# CSI2-ORIN-NANO_Rev01.net
KiCad netlist of a schematic drawn in Altium Designer
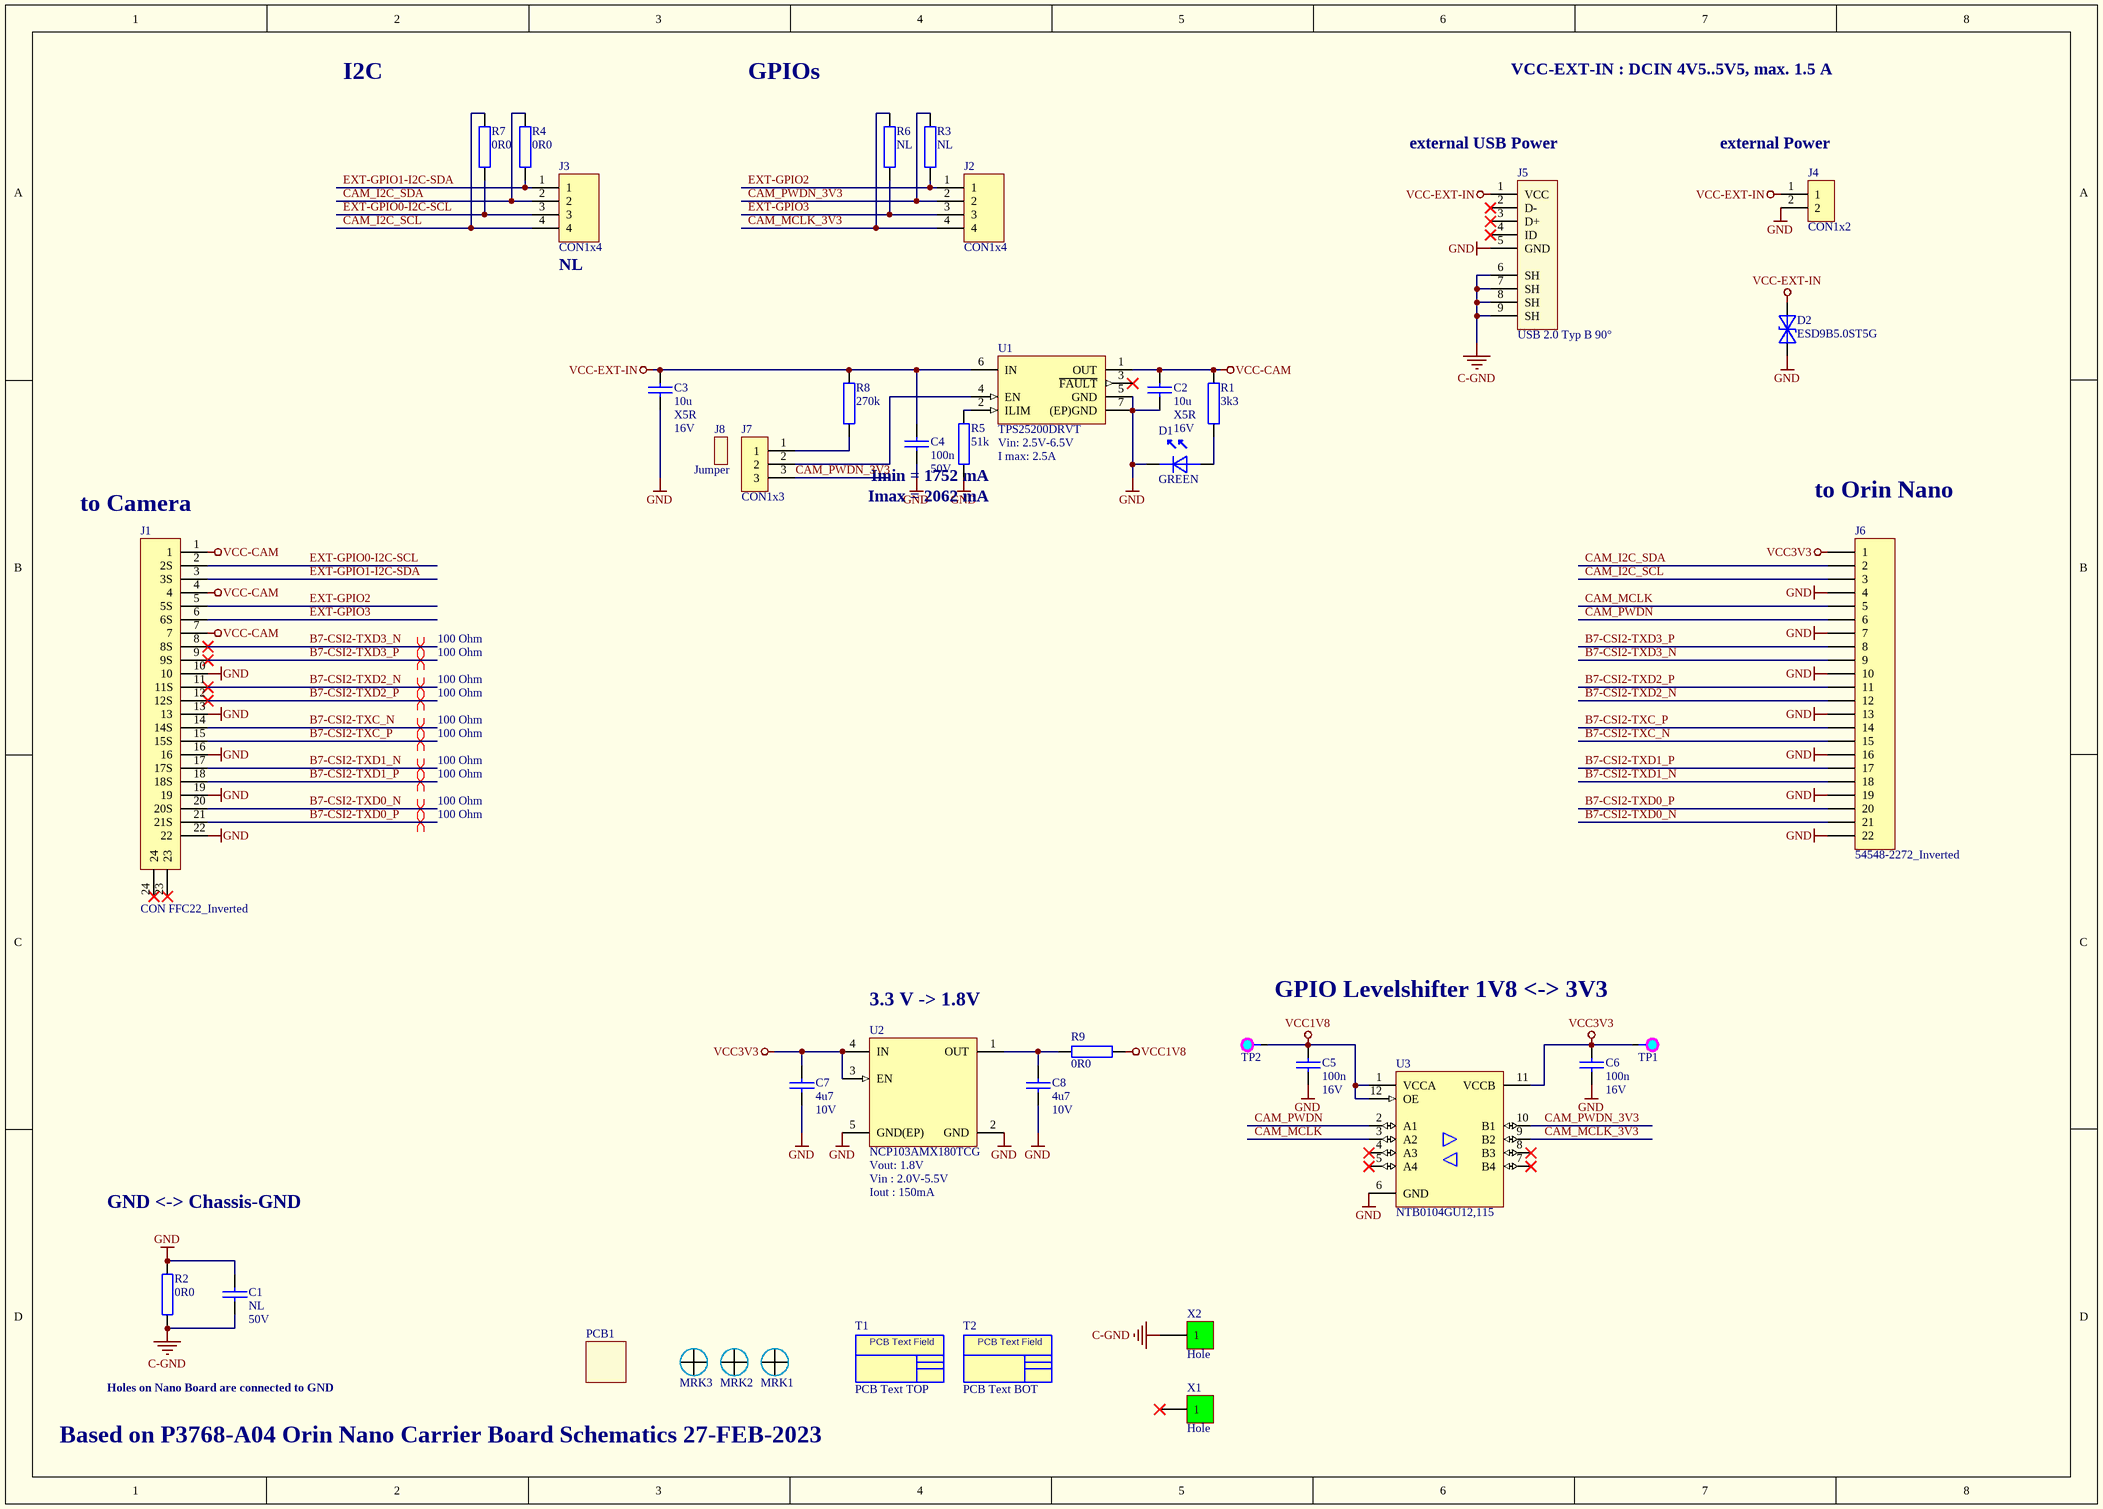
[diagram p0: CSI2-ORIN-NANO_Rev01.SchDoc]

(export (version "E")
  (design (tool "Eeschema 10.0.6"))
  (components
    (comp (ref "C1")
      (value "NL")
      (footprint "C-0603_1.0")
      (description "Capacitor Ceramic SMD/0603/50V/X7R/10%")
      (fields
        (field (name "MANUFACTURER") "several")
        (field (name "TOLERANCE") "10%")
        (field (name "VOLTAGE") "50V")
      )
      (libsource (lib "AVT_KHK_Lib") (part "C X 0603"))
    )
    (comp (ref "C2")
      (value "10u")
      (footprint "C-0805_1.4")
      (description "Capacitor Ceramic SMD/0805/16V/X5R/10%")
      (fields
        (field (name "KHK PART NUMBER") "K8340151")
        (field (name "MANUFACTURER") "several")
        (field (name "DIELECTRIC") "X5R")
        (field (name "VOLTAGE") "16V")
      )
      (libsource (lib "AVT_KHK_Lib") (part "C 10U 16V X5R 0805"))
    )
    (comp (ref "C3")
      (value "10u")
      (footprint "C-0805_1.4")
      (description "Capacitor Ceramic SMD/0805/16V/X5R/10%")
      (fields
        (field (name "KHK PART NUMBER") "K8340151")
        (field (name "MANUFACTURER") "several")
        (field (name "DIELECTRIC") "X5R")
        (field (name "VOLTAGE") "16V")
      )
      (libsource (lib "AVT_KHK_Lib") (part "C 10U 16V X5R 0805"))
    )
    (comp (ref "C4")
      (value "100n")
      (footprint "C-0603_1.0")
      (description "Capacitor Ceramic SMD/0603/50V/X7R/10%")
      (fields
        (field (name "KHK PART NUMBER") "K8340023")
        (field (name "MANUFACTURER") "several")
        (field (name "VOLTAGE") "50V")
      )
      (libsource (lib "AVT_KHK_Lib") (part "C 100N 50V X7R 0603"))
    )
    (comp (ref "C5")
      (value "100n")
      (footprint "C-0402_0.55")
      (description "Capacitor Ceramic SMD/0402/16V/X7R/10%")
      (fields
        (field (name "KHK PART NUMBER") "K8340114")
        (field (name "MANUFACTURER") "several")
        (field (name "VOLTAGE") "16V")
      )
      (libsource (lib "AVT_KHK_Lib") (part "C 100N 10% 16V X7R 402"))
    )
    (comp (ref "C6")
      (value "100n")
      (footprint "C-0402_0.55")
      (description "Capacitor Ceramic SMD/0402/16V/X7R/10%")
      (fields
        (field (name "KHK PART NUMBER") "K8340114")
        (field (name "MANUFACTURER") "several")
        (field (name "VOLTAGE") "16V")
      )
      (libsource (lib "AVT_KHK_Lib") (part "C 100N 10% 16V X7R 402"))
    )
    (comp (ref "C7")
      (value "4u7")
      (footprint "C-0603_1.0")
      (description "Capacitor Ceramic SMD/0603/10V/X5R/10%")
      (fields
        (field (name "KHK PART NUMBER") "1431")
        (field (name "MANUFACTURER") "several")
        (field (name "VOLTAGE") "10V")
      )
      (libsource (lib "AVT_KHK_Lib") (part "C 4U7 10V X5R 0603"))
    )
    (comp (ref "C8")
      (value "4u7")
      (footprint "C-0603_1.0")
      (description "Capacitor Ceramic SMD/0603/10V/X5R/10%")
      (fields
        (field (name "KHK PART NUMBER") "1431")
        (field (name "MANUFACTURER") "several")
        (field (name "VOLTAGE") "10V")
      )
      (libsource (lib "AVT_KHK_Lib") (part "C 4U7 10V X5R 0603"))
    )
    (comp (ref "D1")
      (value "GREEN")
      (footprint "D-0603-LED")
      (description "Chip LED green 430mcd")
      (fields (field (name "KHK PART NUMBER") "8172") (field (name "MANUFACTURER") "Würth"))
      (libsource (lib "AVT_KHK_Lib") (part "D LED 0603 green"))
    )
    (comp (ref "D2")
      (value "ESD9B5.0ST5G")
      (footprint "D-SOD923")
      (description "DIODE TVS; 400W; 5.8-7.8V; BIDIRECT")
      (fields (field (name "KHK PART NUMBER") "7250") (field (name "MANUFACTURER") "ON Semiconductor"))
      (libsource (lib "AVT_KHK_Lib") (part "D ESD9B5.0ST5G"))
    )
    (comp (ref "J1")
      (value "CON FFC22_Inverted")
      (footprint "J-FH55-22S-0.5SH - Inverted Pins")
      (description "FFC Connector 0.5mm shielded")
      (fields
        (field (name "KHK PART NUMBER") "10357")
        (field (name "MANUFACTURER PART NUMBER") "FH55-22S-0.5SH")
      )
      (libsource (lib "AVT_KHK_Lib") (part "CON FFC22_FH55-22S-0.5SH_Inverted"))
    )
    (comp (ref "J2")
      (value "CON1x4")
      (footprint "CON 1x4 RM2.54")
      (fields (field (name "MANUFACTURER") "several") (field (name "KHK PART NUMBER") "15343"))
      (libsource (lib "AVT_KHK_Lib") (part "CON 1x4 2.54 several"))
    )
    (comp (ref "J3")
      (value "CON1x4")
      (footprint "CON 1x4 RM2.54")
      (fields (field (name "MANUFACTURER") "several") (field (name "KHK PART NUMBER") "15343"))
      (libsource (lib "AVT_KHK_Lib") (part "CON 1x4 2.54 several"))
    )
    (comp (ref "J4")
      (value "CON1x2")
      (footprint "CON 1x2 RM2.54")
      (fields (field (name "MANUFACTURER") "several") (field (name "KHK PART NUMBER") "15337"))
      (libsource (lib "AVT_KHK_Lib") (part "CON 1x2 2.54 several"))
    )
    (comp (ref "J5")
      (value "USB 2.0 Typ B 90°")
      (footprint "J-629105150521")
      (description "Micro USB 2.0 Typ B 90°")
      (fields (field (name "KHK PART NUMBER") "14360") (field (name "MANUFACTURER") "WE"))
      (libsource (lib "Connector") (part "CON USB 2.0 Typ B 90°"))
    )
    (comp (ref "J6")
      (value "54548-2272_Inverted")
      (footprint "J-MOLEX-545482272 - INVERTED PINS")
      (description "CON/W2B/FFC;22-pin;0.5mm;SMT;FEMALE;HORIZONTAL")
      (fields (field (name "KHK PART NUMBER") "20137") (field (name "MANUFACTURER PART NUMBER") "54548-2272"))
      (libsource (lib "AVT_KHK_Lib") (part "CON FFC22_54548-2272_Inverted"))
    )
    (comp (ref "J7")
      (value "CON1x3")
      (footprint "CON 1x3 RM2.54")
      (fields (field (name "MANUFACTURER") "several") (field (name "KHK PART NUMBER") "15338"))
      (libsource (lib "AVT_KHK_Lib") (part "CON 1x3 2.54 several"))
    )
    (comp (ref "J8")
      (value "Jumper")
      (footprint "J-JUMPER-2.54")
      (description "CON/JUMPER/STC02SYAN; 2-pin; 2.54mm; 3A; FEMALE; VERTICAL; BLACK")
      (fields (field (name "KHK PART NUMBER") "13444") (field (name "MANUFACTURER") "several"))
      (libsource (lib "AVT_KHK_Lib") (part "CON Jumper 2.54mm"))
    )
    (comp (ref "MRK1")
      (value "Marker Single Layer")
      (footprint "PCB_Marker_Pad_top")
      (description "Position Marker for PCBs")
      (libsource (lib "AVT_KHK_Lib") (part "PCB Marker Pad Single Layer"))
    )
    (comp (ref "MRK2")
      (value "Marker Single Layer")
      (footprint "PCB_Marker_Pad_top")
      (description "Position Marker for PCBs")
      (libsource (lib "AVT_KHK_Lib") (part "PCB Marker Pad Single Layer"))
    )
    (comp (ref "MRK3")
      (value "Marker Single Layer")
      (footprint "PCB_Marker_Pad_top")
      (description "Position Marker for PCBs")
      (libsource (lib "AVT_KHK_Lib") (part "PCB Marker Pad Single Layer"))
    )
    (comp (ref "PCB1")
      (value "~")
      (description "PCB ML04")
      (fields (field (name "MANUFACTURER") "several"))
      (libsource (lib "AVT_KHK_Lib") (part "PCB"))
    )
    (comp (ref "R1")
      (value "3k3")
      (footprint "R-0603_0.6")
      (description "Standard Resistor SMD/0603/1%/100mW/TK100")
      (fields (field (name "KHK PART NUMBER") "K8250070") (field (name "MANUFACTURER") "several"))
      (libsource (lib "AVT_KHK_Lib") (part "R 3K3 1% 0603"))
    )
    (comp (ref "R2")
      (value "0R0")
      (footprint "R-0603_0.6")
      (description "Standard Resistor SMD/0603/1%/100mW/TK200")
      (fields (field (name "KHK PART NUMBER") "K8250041") (field (name "MANUFACTURER") "several"))
      (libsource (lib "AVT_KHK_Lib") (part "R 0R0 1% 0603"))
    )
    (comp (ref "R3")
      (value "NL")
      (footprint "R-0603_0.6")
      (description "Standard Resistor SMD/0603/1%/100mW/TK200")
      (fields (field (name "TOLERANCE") "1%"))
      (libsource (lib "AVT_KHK_Lib") (part "R X 0603"))
    )
    (comp (ref "R4")
      (value "0R0")
      (footprint "R-0603_0.6")
      (description "Standard Resistor SMD/0603/1%/100mW/TK100")
      (fields (field (name "KHK PART NUMBER") "K8250041") (field (name "MANUFACTURER") "several"))
      (libsource (lib "AVT_KHK_Lib") (part "R 0R0 1% 0603"))
    )
    (comp (ref "R5")
      (value "51k")
      (footprint "R-0603_0.6")
      (description "Standard Resistor SMD/0603/1%/100mW/TK100")
      (fields (field (name "KHK PART NUMBER") "K8250156") (field (name "MANUFACTURER") "several"))
      (libsource (lib "AVT_KHK_Lib") (part "R 51K 1% 0603"))
    )
    (comp (ref "R6")
      (value "NL")
      (footprint "R-0603_0.6")
      (description "Standard Resistor SMD/0603/1%/100mW/TK200")
      (fields (field (name "TOLERANCE") "1%"))
      (libsource (lib "AVT_KHK_Lib") (part "R X 0603"))
    )
    (comp (ref "R7")
      (value "0R0")
      (footprint "R-0603_0.6")
      (description "Standard Resistor SMD/0603/1%/100mW/TK100")
      (fields (field (name "KHK PART NUMBER") "K8250041") (field (name "MANUFACTURER") "several"))
      (libsource (lib "AVT_KHK_Lib") (part "R 0R0 1% 0603"))
    )
    (comp (ref "R8")
      (value "270k")
      (footprint "R-0603_0.6")
      (description "Standard Resistor SMD/0603/1%/100mW/TK100")
      (fields (field (name "KHK PART NUMBER") "K8250170") (field (name "MANUFACTURER") "several"))
      (libsource (lib "AVT_KHK_Lib") (part "R 270K 1% 0603"))
    )
    (comp (ref "R9")
      (value "0R0")
      (footprint "R-0603_0.6")
      (description "Standard Resistor SMD/0603/1%/100mW/TK100")
      (fields (field (name "KHK PART NUMBER") "K8250041") (field (name "MANUFACTURER") "several"))
      (libsource (lib "Passive") (part "R 0R0 1% 0603"))
    )
    (comp (ref "T1")
      (value "PCB Text TOP")
      (footprint "PCB TEXTFIELD TOP 2")
      (description "PCB Textfield TOP")
      (libsource (lib "AVT_KHK_Lib") (part "PCB TEXT FIELD TOP"))
    )
    (comp (ref "T2")
      (value "PCB Text BOT")
      (footprint "PCB TEXTFIELD BOT 2")
      (description "PCB Textfield BOT")
      (libsource (lib "AVT_KHK_Lib") (part "PCB TEXT FIELD BOT"))
    )
    (comp (ref "TP1")
      (value "TP")
      (footprint "TP_16_10")
      (description "Testpoint: Pad=1,6mm; Hole=1,0mm")
      (libsource (lib "AVT_KHK_Lib") (part "TP_16_10"))
    )
    (comp (ref "TP2")
      (value "TP")
      (footprint "TP_16_10")
      (description "Testpoint: Pad=1,6mm; Hole=1,0mm")
      (libsource (lib "AVT_KHK_Lib") (part "TP_16_10"))
    )
    (comp (ref "U1")
      (value "TPS25200DRVT")
      (footprint "IC-DFN06_2.0x2.0x0.8")
      (description "IC/PWR/LOADSW;2V5-6V5;2A5;0R099/6-WDFN/2x2x0.8mm")
      (fields
        (field (name "KHK PART NUMBER") "14277")
        (field (name "MANUFACTURER") "Texas Instruments")
        (field (name "VIN") "2.5V-6.5V")
        (field (name "I MAX") "2.5A")
      )
      (libsource (lib "AVT_KHK_Lib") (part "IC  TPS25200DRVT"))
    )
    (comp (ref "U2")
      (value "NCP103AMX180TCG")
      (footprint "IC-XDFN4_1.0x1.0x0.6")
      (description "IC/PWR/LDO;2V0-5V5;1V8;0A150/uDFN4/1x1x0.6mm")
      (fields
        (field (name "KHK PART NUMBER") "14922")
        (field (name "MANUFACTURER") "ON Semi")
        (field (name "VOUT") "1.8V")
        (field (name "VIN") "Vin : 2.0V-5.5V")
        (field (name "IOUT") "Iout : 150mA")
      )
      (libsource (lib "AVT_KHK_Lib") (part "IC NCP103AMX180TCG"))
    )
    (comp (ref "U3")
      (value "NTB0104GU12,115")
      (footprint "IC-XQFN12_1.7x2x0.5")
      (description "IC/LOGIC/Levelshifter;Auto-Dir;Bidirectional;Push-Pull;-40-+125°C/")
      (fields (field (name "MANUFACTURER") "NXP") (field (name "KHK PART NUMBER") "14383"))
      (libsource (lib "AVT_KHK_Lib") (part "IC NTB0104GU12,115"))
    )
    (comp (ref "X1")
      (value "Hole")
      (footprint "HOLE-2.6-5.0-DK")
      (description "HOLE M2.5")
      (libsource (lib "AVT_KHK_Lib") (part "PCB HOLE M2.5-5-DK"))
    )
    (comp (ref "X2")
      (value "Hole")
      (footprint "HOLE-2.6-5.0-DK")
      (description "HOLE M2.5")
      (libsource (lib "AVT_KHK_Lib") (part "PCB HOLE M2.5-5-DK"))
    )
  )
  (nets
    (net (code "1") (name "/B7-CSI2-TXC_N") (class "Default")
      (node (ref "J1") (pin "14") (pinfunction "14S_14") (pintype "passive"))
      (node (ref "J6") (pin "15") (pinfunction "15_15") (pintype "passive"))
    )
    (net (code "2") (name "/B7-CSI2-TXC_P") (class "Default")
      (node (ref "J1") (pin "15") (pinfunction "15S_15") (pintype "passive"))
      (node (ref "J6") (pin "14") (pinfunction "14_14") (pintype "passive"))
    )
    (net (code "3") (name "/B7-CSI2-TXD0_N") (class "Default")
      (node (ref "J1") (pin "20") (pinfunction "20S_20") (pintype "passive"))
      (node (ref "J6") (pin "21") (pinfunction "21_21") (pintype "passive"))
    )
    (net (code "4") (name "/B7-CSI2-TXD0_P") (class "Default")
      (node (ref "J1") (pin "21") (pinfunction "21S_21") (pintype "passive"))
      (node (ref "J6") (pin "20") (pinfunction "20_20") (pintype "passive"))
    )
    (net (code "5") (name "/B7-CSI2-TXD1_N") (class "Default")
      (node (ref "J1") (pin "17") (pinfunction "17S_17") (pintype "passive"))
      (node (ref "J6") (pin "18") (pinfunction "18_18") (pintype "passive"))
    )
    (net (code "6") (name "/B7-CSI2-TXD1_P") (class "Default")
      (node (ref "J1") (pin "18") (pinfunction "18S_18") (pintype "passive"))
      (node (ref "J6") (pin "17") (pinfunction "17_17") (pintype "passive"))
    )
    (net (code "7") (name "/B7-CSI2-TXD2_N") (class "Default")
      (node (ref "J1") (pin "11") (pinfunction "11S_11") (pintype "passive"))
      (node (ref "J6") (pin "12") (pinfunction "12_12") (pintype "passive"))
    )
    (net (code "8") (name "/B7-CSI2-TXD2_P") (class "Default")
      (node (ref "J1") (pin "12") (pinfunction "12S_12") (pintype "passive"))
      (node (ref "J6") (pin "11") (pinfunction "11_11") (pintype "passive"))
    )
    (net (code "9") (name "/B7-CSI2-TXD3_N") (class "Default")
      (node (ref "J1") (pin "8") (pinfunction "8S_8") (pintype "passive"))
      (node (ref "J6") (pin "9") (pinfunction "9_9") (pintype "passive"))
    )
    (net (code "10") (name "/B7-CSI2-TXD3_P") (class "Default")
      (node (ref "J1") (pin "9") (pinfunction "9S_9") (pintype "passive"))
      (node (ref "J6") (pin "8") (pinfunction "8_8") (pintype "passive"))
    )
    (net (code "11") (name "/CAM_I2C_SCL") (class "Default")
      (node (ref "J3") (pin "4") (pinfunction "4_4") (pintype "passive"))
      (node (ref "J6") (pin "3") (pinfunction "3_3") (pintype "passive"))
      (node (ref "R7") (pin "2") (pinfunction "2_2") (pintype "passive"))
    )
    (net (code "12") (name "/CAM_I2C_SDA") (class "Default")
      (node (ref "J3") (pin "2") (pinfunction "2_2") (pintype "passive"))
      (node (ref "J6") (pin "2") (pinfunction "2_2") (pintype "passive"))
      (node (ref "R4") (pin "2") (pinfunction "2_2") (pintype "passive"))
    )
    (net (code "13") (name "/CAM_MCLK") (class "Default")
      (node (ref "J6") (pin "5") (pinfunction "5_5") (pintype "passive"))
      (node (ref "U3") (pin "3") (pinfunction "A2_3") (pintype "bidirectional"))
    )
    (net (code "14") (name "/CAM_MCLK_3V3") (class "Default")
      (node (ref "J2") (pin "4") (pinfunction "4_4") (pintype "passive"))
      (node (ref "R6") (pin "2") (pinfunction "2_2") (pintype "passive"))
      (node (ref "U3") (pin "9") (pinfunction "B2_9") (pintype "bidirectional"))
    )
    (net (code "15") (name "/CAM_PWDN") (class "Default")
      (node (ref "J6") (pin "6") (pinfunction "6_6") (pintype "passive"))
      (node (ref "U3") (pin "2") (pinfunction "A1_2") (pintype "bidirectional"))
    )
    (net (code "16") (name "/CAM_PWDN_3V3") (class "Default")
      (node (ref "J2") (pin "2") (pinfunction "2_2") (pintype "passive"))
      (node (ref "J7") (pin "3") (pinfunction "3_3") (pintype "passive"))
      (node (ref "R3") (pin "2") (pinfunction "2_2") (pintype "passive"))
      (node (ref "U3") (pin "10") (pinfunction "B1_10") (pintype "bidirectional"))
    )
    (net (code "17") (name "/EXT-GPIO0-I2C-SCL") (class "Default")
      (node (ref "J1") (pin "2") (pinfunction "2S_2") (pintype "passive"))
      (node (ref "J3") (pin "3") (pinfunction "3_3") (pintype "passive"))
      (node (ref "R7") (pin "1") (pinfunction "1_1") (pintype "passive"))
    )
    (net (code "18") (name "/EXT-GPIO1-I2C-SDA") (class "Default")
      (node (ref "J1") (pin "3") (pinfunction "3S_3") (pintype "passive"))
      (node (ref "J3") (pin "1") (pinfunction "1_1") (pintype "passive"))
      (node (ref "R4") (pin "1") (pinfunction "1_1") (pintype "passive"))
    )
    (net (code "19") (name "/EXT-GPIO2") (class "Default")
      (node (ref "J1") (pin "5") (pinfunction "5S_5") (pintype "passive"))
      (node (ref "J2") (pin "1") (pinfunction "1_1") (pintype "passive"))
      (node (ref "R3") (pin "1") (pinfunction "1_1") (pintype "passive"))
    )
    (net (code "20") (name "/EXT-GPIO3") (class "Default")
      (node (ref "J1") (pin "6") (pinfunction "6S_6") (pintype "passive"))
      (node (ref "J2") (pin "3") (pinfunction "3_3") (pintype "passive"))
      (node (ref "R6") (pin "1") (pinfunction "1_1") (pintype "passive"))
    )
    (net (code "21") (name "C-GND") (class "Default")
      (node (ref "C1") (pin "2") (pinfunction "2_2") (pintype "passive"))
      (node (ref "J5") (pin "6") (pinfunction "SH_6") (pintype "passive"))
      (node (ref "J5") (pin "7") (pinfunction "SH_7") (pintype "passive"))
      (node (ref "J5") (pin "8") (pinfunction "SH_8") (pintype "passive"))
      (node (ref "J5") (pin "9") (pinfunction "SH_9") (pintype "passive"))
      (node (ref "R2") (pin "1") (pinfunction "1_1") (pintype "passive"))
      (node (ref "X2") (pin "1") (pinfunction "1_1") (pintype "passive"))
    )
    (net (code "22") (name "GND") (class "Default")
      (node (ref "C1") (pin "1") (pinfunction "1_1") (pintype "passive"))
      (node (ref "C2") (pin "2") (pinfunction "2_2") (pintype "passive"))
      (node (ref "C3") (pin "2") (pinfunction "2_2") (pintype "passive"))
      (node (ref "C4") (pin "2") (pinfunction "2_2") (pintype "passive"))
      (node (ref "C5") (pin "2") (pinfunction "2_2") (pintype "passive"))
      (node (ref "C6") (pin "2") (pinfunction "2_2") (pintype "passive"))
      (node (ref "C7") (pin "2") (pinfunction "2_2") (pintype "passive"))
      (node (ref "C8") (pin "2") (pinfunction "2_2") (pintype "passive"))
      (node (ref "D1") (pin "K") (pinfunction "2_K") (pintype "passive"))
      (node (ref "D2") (pin "A") (pinfunction "A_A") (pintype "passive"))
      (node (ref "J1") (pin "10") (pinfunction "10_10") (pintype "passive"))
      (node (ref "J1") (pin "13") (pinfunction "13_13") (pintype "passive"))
      (node (ref "J1") (pin "16") (pinfunction "16_16") (pintype "passive"))
      (node (ref "J1") (pin "19") (pinfunction "19_19") (pintype "passive"))
      (node (ref "J1") (pin "22") (pinfunction "22_22") (pintype "passive"))
      (node (ref "J4") (pin "2") (pinfunction "2_2") (pintype "passive"))
      (node (ref "J5") (pin "5") (pinfunction "GND_5") (pintype "passive"))
      (node (ref "J6") (pin "10") (pinfunction "10_10") (pintype "passive"))
      (node (ref "J6") (pin "13") (pinfunction "13_13") (pintype "passive"))
      (node (ref "J6") (pin "16") (pinfunction "16_16") (pintype "passive"))
      (node (ref "J6") (pin "19") (pinfunction "19_19") (pintype "passive"))
      (node (ref "J6") (pin "22") (pinfunction "22_22") (pintype "passive"))
      (node (ref "J6") (pin "4") (pinfunction "4_4") (pintype "passive"))
      (node (ref "J6") (pin "7") (pinfunction "7_7") (pintype "passive"))
      (node (ref "R2") (pin "2") (pinfunction "2_2") (pintype "passive"))
      (node (ref "R5") (pin "1") (pinfunction "1_1") (pintype "passive"))
      (node (ref "U1") (pin "5") (pinfunction "GND_5") (pintype "power_in"))
      (node (ref "U1") (pin "7") (pinfunction "(EP)GND_7") (pintype "power_in"))
      (node (ref "U2") (pin "2") (pinfunction "GND_2") (pintype "power_in"))
      (node (ref "U2") (pin "5") (pinfunction "GND(EP)_5") (pintype "power_in"))
      (node (ref "U3") (pin "6") (pinfunction "GND_6") (pintype "power_in"))
    )
    (net (code "23") (name "Net-(D1-1)") (class "Default")
      (node (ref "D1") (pin "A") (pinfunction "1_A") (pintype "passive"))
      (node (ref "R1") (pin "2") (pinfunction "2_2") (pintype "passive"))
    )
    (net (code "24") (name "Net-(J7-Pad1)") (class "Default")
      (node (ref "J7") (pin "1") (pinfunction "1_1") (pintype "passive"))
      (node (ref "R8") (pin "2") (pinfunction "2_2") (pintype "passive"))
    )
    (net (code "25") (name "Net-(U1-EN)") (class "Default")
      (node (ref "J7") (pin "2") (pinfunction "2_2") (pintype "passive"))
      (node (ref "U1") (pin "4") (pinfunction "EN_4") (pintype "input"))
    )
    (net (code "26") (name "Net-(U1-ILIM)") (class "Default")
      (node (ref "R5") (pin "2") (pinfunction "2_2") (pintype "passive"))
      (node (ref "U1") (pin "2") (pinfunction "ILIM_2") (pintype "input"))
    )
    (net (code "27") (name "Net-(U2-OUT)") (class "Default")
      (node (ref "C8") (pin "1") (pinfunction "1_1") (pintype "passive"))
      (node (ref "R9") (pin "1") (pinfunction "1_1") (pintype "passive"))
      (node (ref "U2") (pin "1") (pinfunction "OUT_1") (pintype "power_in"))
    )
    (net (code "28") (name "VCC-CAM") (class "Default")
      (node (ref "C2") (pin "1") (pinfunction "1_1") (pintype "passive"))
      (node (ref "J1") (pin "1") (pinfunction "1_1") (pintype "passive"))
      (node (ref "J1") (pin "4") (pinfunction "4_4") (pintype "passive"))
      (node (ref "J1") (pin "7") (pinfunction "7_7") (pintype "passive"))
      (node (ref "R1") (pin "1") (pinfunction "1_1") (pintype "passive"))
      (node (ref "U1") (pin "1") (pinfunction "OUT_1") (pintype "power_in"))
    )
    (net (code "29") (name "VCC-EXT-IN") (class "Default")
      (node (ref "C3") (pin "1") (pinfunction "1_1") (pintype "passive"))
      (node (ref "C4") (pin "1") (pinfunction "1_1") (pintype "passive"))
      (node (ref "D2") (pin "K") (pinfunction "K_K") (pintype "passive"))
      (node (ref "J4") (pin "1") (pinfunction "1_1") (pintype "passive"))
      (node (ref "J5") (pin "1") (pinfunction "VCC_1") (pintype "passive"))
      (node (ref "R8") (pin "1") (pinfunction "1_1") (pintype "passive"))
      (node (ref "U1") (pin "6") (pinfunction "IN_6") (pintype "power_in"))
    )
    (net (code "30") (name "VCC1V8") (class "Default")
      (node (ref "C5") (pin "1") (pinfunction "1_1") (pintype "passive"))
      (node (ref "R9") (pin "2") (pinfunction "2_2") (pintype "passive"))
      (node (ref "TP2") (pin "1") (pinfunction "1_1") (pintype "passive"))
      (node (ref "U3") (pin "1") (pinfunction "VCCA_1") (pintype "power_in"))
      (node (ref "U3") (pin "12") (pinfunction "OE_12") (pintype "input"))
    )
    (net (code "31") (name "VCC3V3") (class "Default")
      (node (ref "C6") (pin "1") (pinfunction "1_1") (pintype "passive"))
      (node (ref "C7") (pin "1") (pinfunction "1_1") (pintype "passive"))
      (node (ref "J6") (pin "1") (pinfunction "1_1") (pintype "passive"))
      (node (ref "TP1") (pin "1") (pinfunction "1_1") (pintype "passive"))
      (node (ref "U2") (pin "3") (pinfunction "EN_3") (pintype "input"))
      (node (ref "U2") (pin "4") (pinfunction "IN_4") (pintype "power_in"))
      (node (ref "U3") (pin "11") (pinfunction "VCCB_11") (pintype "power_in"))
    )
    (net (code "32") (name "unconnected-(J1-Pad23)") (class "Default")
      (node (ref "J1") (pin "23") (pinfunction "23_23") (pintype "passive+no_connect"))
    )
    (net (code "33") (name "unconnected-(J1-Pad24)") (class "Default")
      (node (ref "J1") (pin "24") (pinfunction "24_24") (pintype "passive+no_connect"))
    )
    (net (code "34") (name "unconnected-(J5-D+-Pad3)") (class "Default")
      (node (ref "J5") (pin "3") (pinfunction "D+_3") (pintype "passive+no_connect"))
    )
    (net (code "35") (name "unconnected-(J5-D--Pad2)") (class "Default")
      (node (ref "J5") (pin "2") (pinfunction "D-_2") (pintype "passive+no_connect"))
    )
    (net (code "36") (name "unconnected-(J5-ID-Pad4)") (class "Default")
      (node (ref "J5") (pin "4") (pinfunction "ID_4") (pintype "passive+no_connect"))
    )
    (net (code "37") (name "unconnected-(U1-~{FAULT}-Pad3)") (class "Default")
      (node (ref "U1") (pin "3") (pinfunction "~{FAULT}_3") (pintype "output+no_connect"))
    )
    (net (code "38") (name "unconnected-(U3-A3-Pad4)") (class "Default")
      (node (ref "U3") (pin "4") (pinfunction "A3_4") (pintype "bidirectional+no_connect"))
    )
    (net (code "39") (name "unconnected-(U3-A4-Pad5)") (class "Default")
      (node (ref "U3") (pin "5") (pinfunction "A4_5") (pintype "bidirectional+no_connect"))
    )
    (net (code "40") (name "unconnected-(U3-B3-Pad8)") (class "Default")
      (node (ref "U3") (pin "8") (pinfunction "B3_8") (pintype "bidirectional+no_connect"))
    )
    (net (code "41") (name "unconnected-(U3-B4-Pad7)") (class "Default")
      (node (ref "U3") (pin "7") (pinfunction "B4_7") (pintype "bidirectional+no_connect"))
    )
    (net (code "42") (name "unconnected-(X1-Pad1)") (class "Default")
      (node (ref "X1") (pin "1") (pinfunction "1_1") (pintype "passive+no_connect"))
    )
  )
)
